# tdt_maleToMale.net
KiCad netlist of a schematic drawn in EAGLE
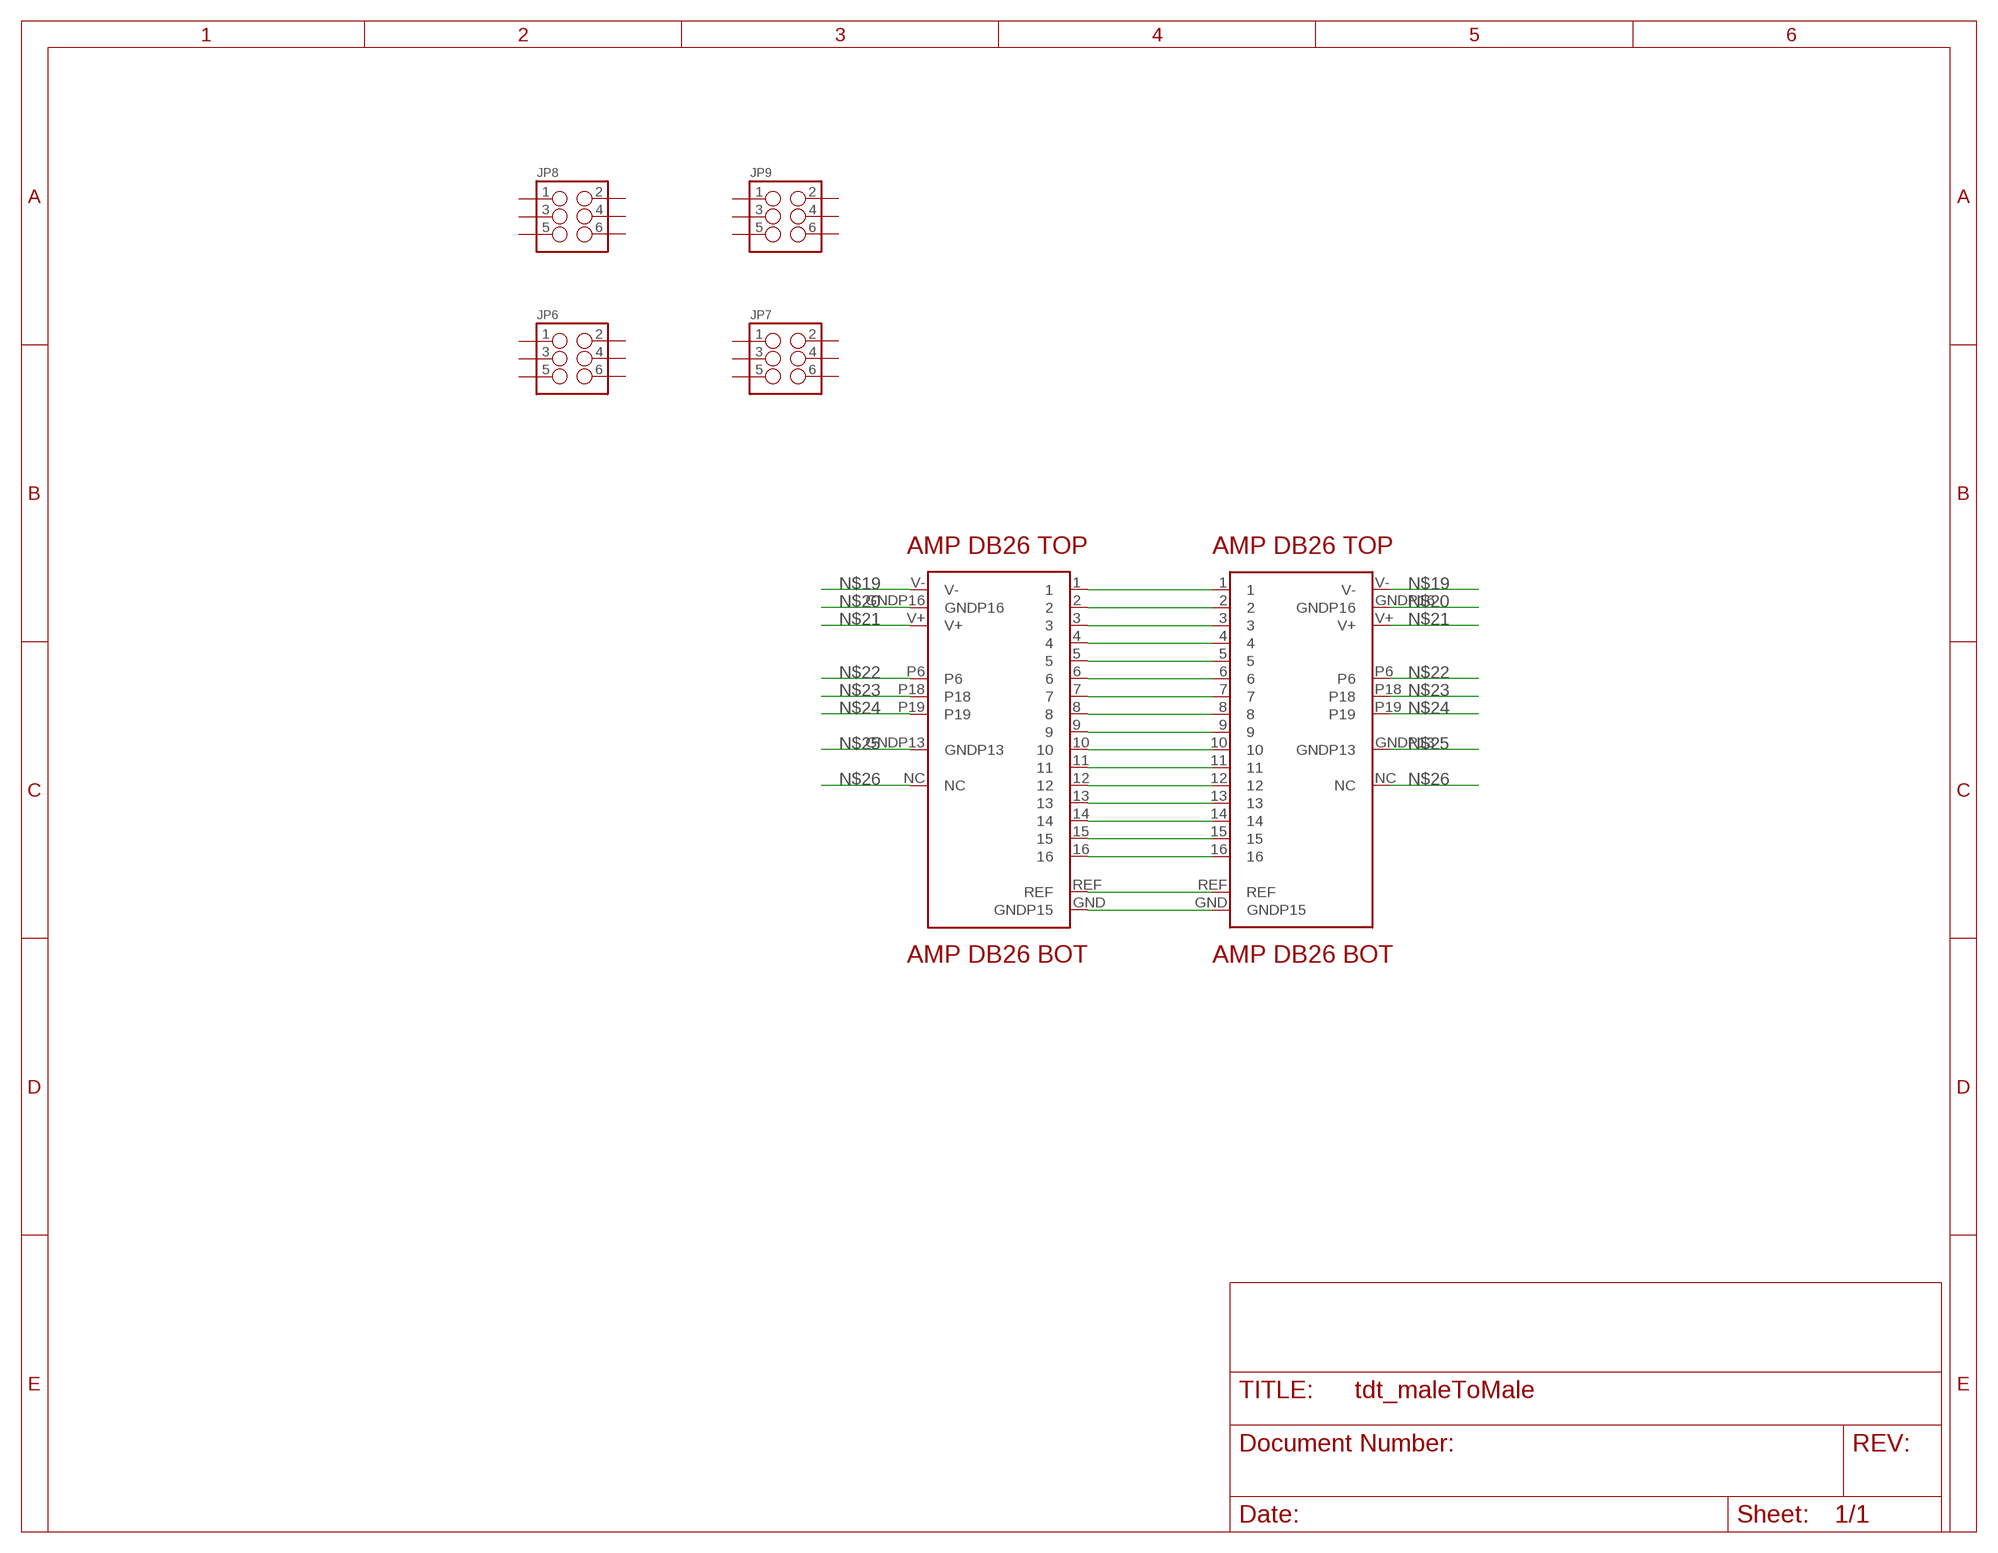
[diagram p0: schematic, sheet 1]

(export (version "E")
  (design (tool "Eeschema 10.0.6"))
  (components
    (comp (ref "JP6")
      (value "M03X22X3_SILK_MALE_PTH")
      (footprint "eagle-import:2X3")
      (libsource (lib "eagle-import") (part "M03X22X3_SILK_MALE_PTH"))
    )
    (comp (ref "JP7")
      (value "M03X22X3_SILK_MALE_PTH")
      (footprint "eagle-import:2X3")
      (libsource (lib "eagle-import") (part "M03X22X3_SILK_MALE_PTH"))
    )
    (comp (ref "JP8")
      (value "M03X22X3_SILK_MALE_PTH")
      (footprint "eagle-import:2X3")
      (libsource (lib "eagle-import") (part "M03X22X3_SILK_MALE_PTH"))
    )
    (comp (ref "JP9")
      (value "M03X22X3_SILK_MALE_PTH")
      (footprint "eagle-import:2X3")
      (libsource (lib "eagle-import") (part "M03X22X3_SILK_MALE_PTH"))
    )
    (comp (ref "U$1")
      (value "DB26-MALE-BOT")
      (footprint "eagle-import:DB26-MALE-BOT")
      (libsource (lib "eagle-import") (part "DB26-MALE-BOT"))
    )
    (comp (ref "U$2")
      (value "DB26-MALE-TOP")
      (footprint "eagle-import:DB26-MALE-TOP")
      (libsource (lib "eagle-import") (part "DB26-MALE-TOP"))
    )
    (comp (ref "U$3")
      (value "DB26-MALE-TOP")
      (footprint "eagle-import:DB26-MALE-TOP")
      (libsource (lib "eagle-import") (part "DB26-MALE-TOP"))
    )
    (comp (ref "U$4")
      (value "DB26-MALE-BOT")
      (footprint "eagle-import:DB26-MALE-BOT")
      (libsource (lib "eagle-import") (part "DB26-MALE-BOT"))
    )
  )
  (nets
    (net (code "1") (name "/N$19") (class "Default")
      (node (ref "U$1") (pin "V-") (pinfunction "V-_V-") (pintype "bidirectional"))
      (node (ref "U$4") (pin "V-") (pinfunction "V-_V-") (pintype "bidirectional"))
    )
    (net (code "2") (name "/N$20") (class "Default")
      (node (ref "U$1") (pin "GNDP16") (pinfunction "GNDP16_GNDP16") (pintype "bidirectional"))
      (node (ref "U$4") (pin "GNDP16") (pinfunction "GNDP16_GNDP16") (pintype "bidirectional"))
    )
    (net (code "3") (name "/N$21") (class "Default")
      (node (ref "U$1") (pin "V+") (pinfunction "V+_V+") (pintype "bidirectional"))
      (node (ref "U$4") (pin "V+") (pinfunction "V+_V+") (pintype "bidirectional"))
    )
    (net (code "4") (name "/N$22") (class "Default")
      (node (ref "U$2") (pin "P6") (pinfunction "P6_P6") (pintype "bidirectional"))
      (node (ref "U$3") (pin "P6") (pinfunction "P6_P6") (pintype "bidirectional"))
    )
    (net (code "5") (name "/N$23") (class "Default")
      (node (ref "U$1") (pin "P18") (pinfunction "P18_P18") (pintype "bidirectional"))
      (node (ref "U$4") (pin "P18") (pinfunction "P18_P18") (pintype "bidirectional"))
    )
    (net (code "6") (name "/N$24") (class "Default")
      (node (ref "U$1") (pin "P19") (pinfunction "P19_P19") (pintype "bidirectional"))
      (node (ref "U$4") (pin "P19") (pinfunction "P19_P19") (pintype "bidirectional"))
    )
    (net (code "7") (name "/N$25") (class "Default")
      (node (ref "U$2") (pin "GNDP13") (pinfunction "GNDP13_GNDP13") (pintype "bidirectional"))
      (node (ref "U$3") (pin "GNDP13") (pinfunction "GNDP13_GNDP13") (pintype "bidirectional"))
    )
    (net (code "8") (name "/N$26") (class "Default")
      (node (ref "U$1") (pin "NC") (pinfunction "NC_NC") (pintype "bidirectional"))
      (node (ref "U$4") (pin "NC") (pinfunction "NC_NC") (pintype "bidirectional"))
    )
    (net (code "9") (name "Net-(U$1-GNDP15)") (class "Default")
      (node (ref "U$1") (pin "GND") (pinfunction "GNDP15_GND") (pintype "bidirectional"))
      (node (ref "U$4") (pin "GND") (pinfunction "GNDP15_GND") (pintype "bidirectional"))
    )
    (net (code "10") (name "Net-(U$1-Pad6)") (class "Default")
      (node (ref "U$1") (pin "6") (pinfunction "6_6") (pintype "bidirectional"))
      (node (ref "U$4") (pin "6") (pinfunction "6_6") (pintype "bidirectional"))
    )
    (net (code "11") (name "Net-(U$1-Pad8)") (class "Default")
      (node (ref "U$1") (pin "8") (pinfunction "8_8") (pintype "bidirectional"))
      (node (ref "U$4") (pin "8") (pinfunction "8_8") (pintype "bidirectional"))
    )
    (net (code "12") (name "Net-(U$1-Pad10)") (class "Default")
      (node (ref "U$1") (pin "10") (pinfunction "10_10") (pintype "bidirectional"))
      (node (ref "U$4") (pin "10") (pinfunction "10_10") (pintype "bidirectional"))
    )
    (net (code "13") (name "Net-(U$1-Pad12)") (class "Default")
      (node (ref "U$1") (pin "12") (pinfunction "12_12") (pintype "bidirectional"))
      (node (ref "U$4") (pin "12") (pinfunction "12_12") (pintype "bidirectional"))
    )
    (net (code "14") (name "Net-(U$1-Pad14)") (class "Default")
      (node (ref "U$1") (pin "14") (pinfunction "14_14") (pintype "bidirectional"))
      (node (ref "U$4") (pin "14") (pinfunction "14_14") (pintype "bidirectional"))
    )
    (net (code "15") (name "Net-(U$1-Pad16)") (class "Default")
      (node (ref "U$1") (pin "16") (pinfunction "16_16") (pintype "bidirectional"))
      (node (ref "U$4") (pin "16") (pinfunction "16_16") (pintype "bidirectional"))
    )
    (net (code "16") (name "Net-(U$2-Pad1)") (class "Default")
      (node (ref "U$2") (pin "1") (pinfunction "1_1") (pintype "bidirectional"))
      (node (ref "U$3") (pin "1") (pinfunction "1_1") (pintype "bidirectional"))
    )
    (net (code "17") (name "Net-(U$2-Pad2)") (class "Default")
      (node (ref "U$2") (pin "2") (pinfunction "2_2") (pintype "bidirectional"))
      (node (ref "U$3") (pin "2") (pinfunction "2_2") (pintype "bidirectional"))
    )
    (net (code "18") (name "Net-(U$2-Pad3)") (class "Default")
      (node (ref "U$2") (pin "3") (pinfunction "3_3") (pintype "bidirectional"))
      (node (ref "U$3") (pin "3") (pinfunction "3_3") (pintype "bidirectional"))
    )
    (net (code "19") (name "Net-(U$2-Pad4)") (class "Default")
      (node (ref "U$2") (pin "4") (pinfunction "4_4") (pintype "bidirectional"))
      (node (ref "U$3") (pin "4") (pinfunction "4_4") (pintype "bidirectional"))
    )
    (net (code "20") (name "Net-(U$2-Pad5)") (class "Default")
      (node (ref "U$2") (pin "5") (pinfunction "5_5") (pintype "bidirectional"))
      (node (ref "U$3") (pin "5") (pinfunction "5_5") (pintype "bidirectional"))
    )
    (net (code "21") (name "Net-(U$2-Pad7)") (class "Default")
      (node (ref "U$2") (pin "7") (pinfunction "7_7") (pintype "bidirectional"))
      (node (ref "U$3") (pin "7") (pinfunction "7_7") (pintype "bidirectional"))
    )
    (net (code "22") (name "Net-(U$2-Pad9)") (class "Default")
      (node (ref "U$2") (pin "9") (pinfunction "9_9") (pintype "bidirectional"))
      (node (ref "U$3") (pin "9") (pinfunction "9_9") (pintype "bidirectional"))
    )
    (net (code "23") (name "Net-(U$2-Pad11)") (class "Default")
      (node (ref "U$2") (pin "11") (pinfunction "11_11") (pintype "bidirectional"))
      (node (ref "U$3") (pin "11") (pinfunction "11_11") (pintype "bidirectional"))
    )
    (net (code "24") (name "Net-(U$2-Pad13)") (class "Default")
      (node (ref "U$2") (pin "13") (pinfunction "13_13") (pintype "bidirectional"))
      (node (ref "U$3") (pin "13") (pinfunction "13_13") (pintype "bidirectional"))
    )
    (net (code "25") (name "Net-(U$2-Pad15)") (class "Default")
      (node (ref "U$2") (pin "15") (pinfunction "15_15") (pintype "bidirectional"))
      (node (ref "U$3") (pin "15") (pinfunction "15_15") (pintype "bidirectional"))
    )
    (net (code "26") (name "Net-(U$2-PadREF)") (class "Default")
      (node (ref "U$2") (pin "REF") (pinfunction "REF_REF") (pintype "bidirectional"))
      (node (ref "U$3") (pin "REF") (pinfunction "REF_REF") (pintype "bidirectional"))
    )
    (net (code "27") (name "unconnected-(JP6-Pad1)") (class "Default")
      (node (ref "JP6") (pin "1") (pinfunction "1_1") (pintype "bidirectional"))
    )
    (net (code "28") (name "unconnected-(JP6-Pad2)") (class "Default")
      (node (ref "JP6") (pin "2") (pinfunction "2_2") (pintype "bidirectional"))
    )
    (net (code "29") (name "unconnected-(JP6-Pad3)") (class "Default")
      (node (ref "JP6") (pin "3") (pinfunction "3_3") (pintype "bidirectional"))
    )
    (net (code "30") (name "unconnected-(JP6-Pad4)") (class "Default")
      (node (ref "JP6") (pin "4") (pinfunction "4_4") (pintype "bidirectional"))
    )
    (net (code "31") (name "unconnected-(JP6-Pad5)") (class "Default")
      (node (ref "JP6") (pin "5") (pinfunction "5_5") (pintype "bidirectional"))
    )
    (net (code "32") (name "unconnected-(JP6-Pad6)") (class "Default")
      (node (ref "JP6") (pin "6") (pinfunction "6_6") (pintype "bidirectional"))
    )
    (net (code "33") (name "unconnected-(JP7-Pad1)") (class "Default")
      (node (ref "JP7") (pin "1") (pinfunction "1_1") (pintype "bidirectional"))
    )
    (net (code "34") (name "unconnected-(JP7-Pad2)") (class "Default")
      (node (ref "JP7") (pin "2") (pinfunction "2_2") (pintype "bidirectional"))
    )
    (net (code "35") (name "unconnected-(JP7-Pad3)") (class "Default")
      (node (ref "JP7") (pin "3") (pinfunction "3_3") (pintype "bidirectional"))
    )
    (net (code "36") (name "unconnected-(JP7-Pad4)") (class "Default")
      (node (ref "JP7") (pin "4") (pinfunction "4_4") (pintype "bidirectional"))
    )
    (net (code "37") (name "unconnected-(JP7-Pad5)") (class "Default")
      (node (ref "JP7") (pin "5") (pinfunction "5_5") (pintype "bidirectional"))
    )
    (net (code "38") (name "unconnected-(JP7-Pad6)") (class "Default")
      (node (ref "JP7") (pin "6") (pinfunction "6_6") (pintype "bidirectional"))
    )
    (net (code "39") (name "unconnected-(JP8-Pad1)") (class "Default")
      (node (ref "JP8") (pin "1") (pinfunction "1_1") (pintype "bidirectional"))
    )
    (net (code "40") (name "unconnected-(JP8-Pad2)") (class "Default")
      (node (ref "JP8") (pin "2") (pinfunction "2_2") (pintype "bidirectional"))
    )
    (net (code "41") (name "unconnected-(JP8-Pad3)") (class "Default")
      (node (ref "JP8") (pin "3") (pinfunction "3_3") (pintype "bidirectional"))
    )
    (net (code "42") (name "unconnected-(JP8-Pad4)") (class "Default")
      (node (ref "JP8") (pin "4") (pinfunction "4_4") (pintype "bidirectional"))
    )
    (net (code "43") (name "unconnected-(JP8-Pad5)") (class "Default")
      (node (ref "JP8") (pin "5") (pinfunction "5_5") (pintype "bidirectional"))
    )
    (net (code "44") (name "unconnected-(JP8-Pad6)") (class "Default")
      (node (ref "JP8") (pin "6") (pinfunction "6_6") (pintype "bidirectional"))
    )
    (net (code "45") (name "unconnected-(JP9-Pad1)") (class "Default")
      (node (ref "JP9") (pin "1") (pinfunction "1_1") (pintype "bidirectional"))
    )
    (net (code "46") (name "unconnected-(JP9-Pad2)") (class "Default")
      (node (ref "JP9") (pin "2") (pinfunction "2_2") (pintype "bidirectional"))
    )
    (net (code "47") (name "unconnected-(JP9-Pad3)") (class "Default")
      (node (ref "JP9") (pin "3") (pinfunction "3_3") (pintype "bidirectional"))
    )
    (net (code "48") (name "unconnected-(JP9-Pad4)") (class "Default")
      (node (ref "JP9") (pin "4") (pinfunction "4_4") (pintype "bidirectional"))
    )
    (net (code "49") (name "unconnected-(JP9-Pad5)") (class "Default")
      (node (ref "JP9") (pin "5") (pinfunction "5_5") (pintype "bidirectional"))
    )
    (net (code "50") (name "unconnected-(JP9-Pad6)") (class "Default")
      (node (ref "JP9") (pin "6") (pinfunction "6_6") (pintype "bidirectional"))
    )
  )
)
